# Flutter-v1.net
KiCad netlist of a schematic drawn in EAGLE
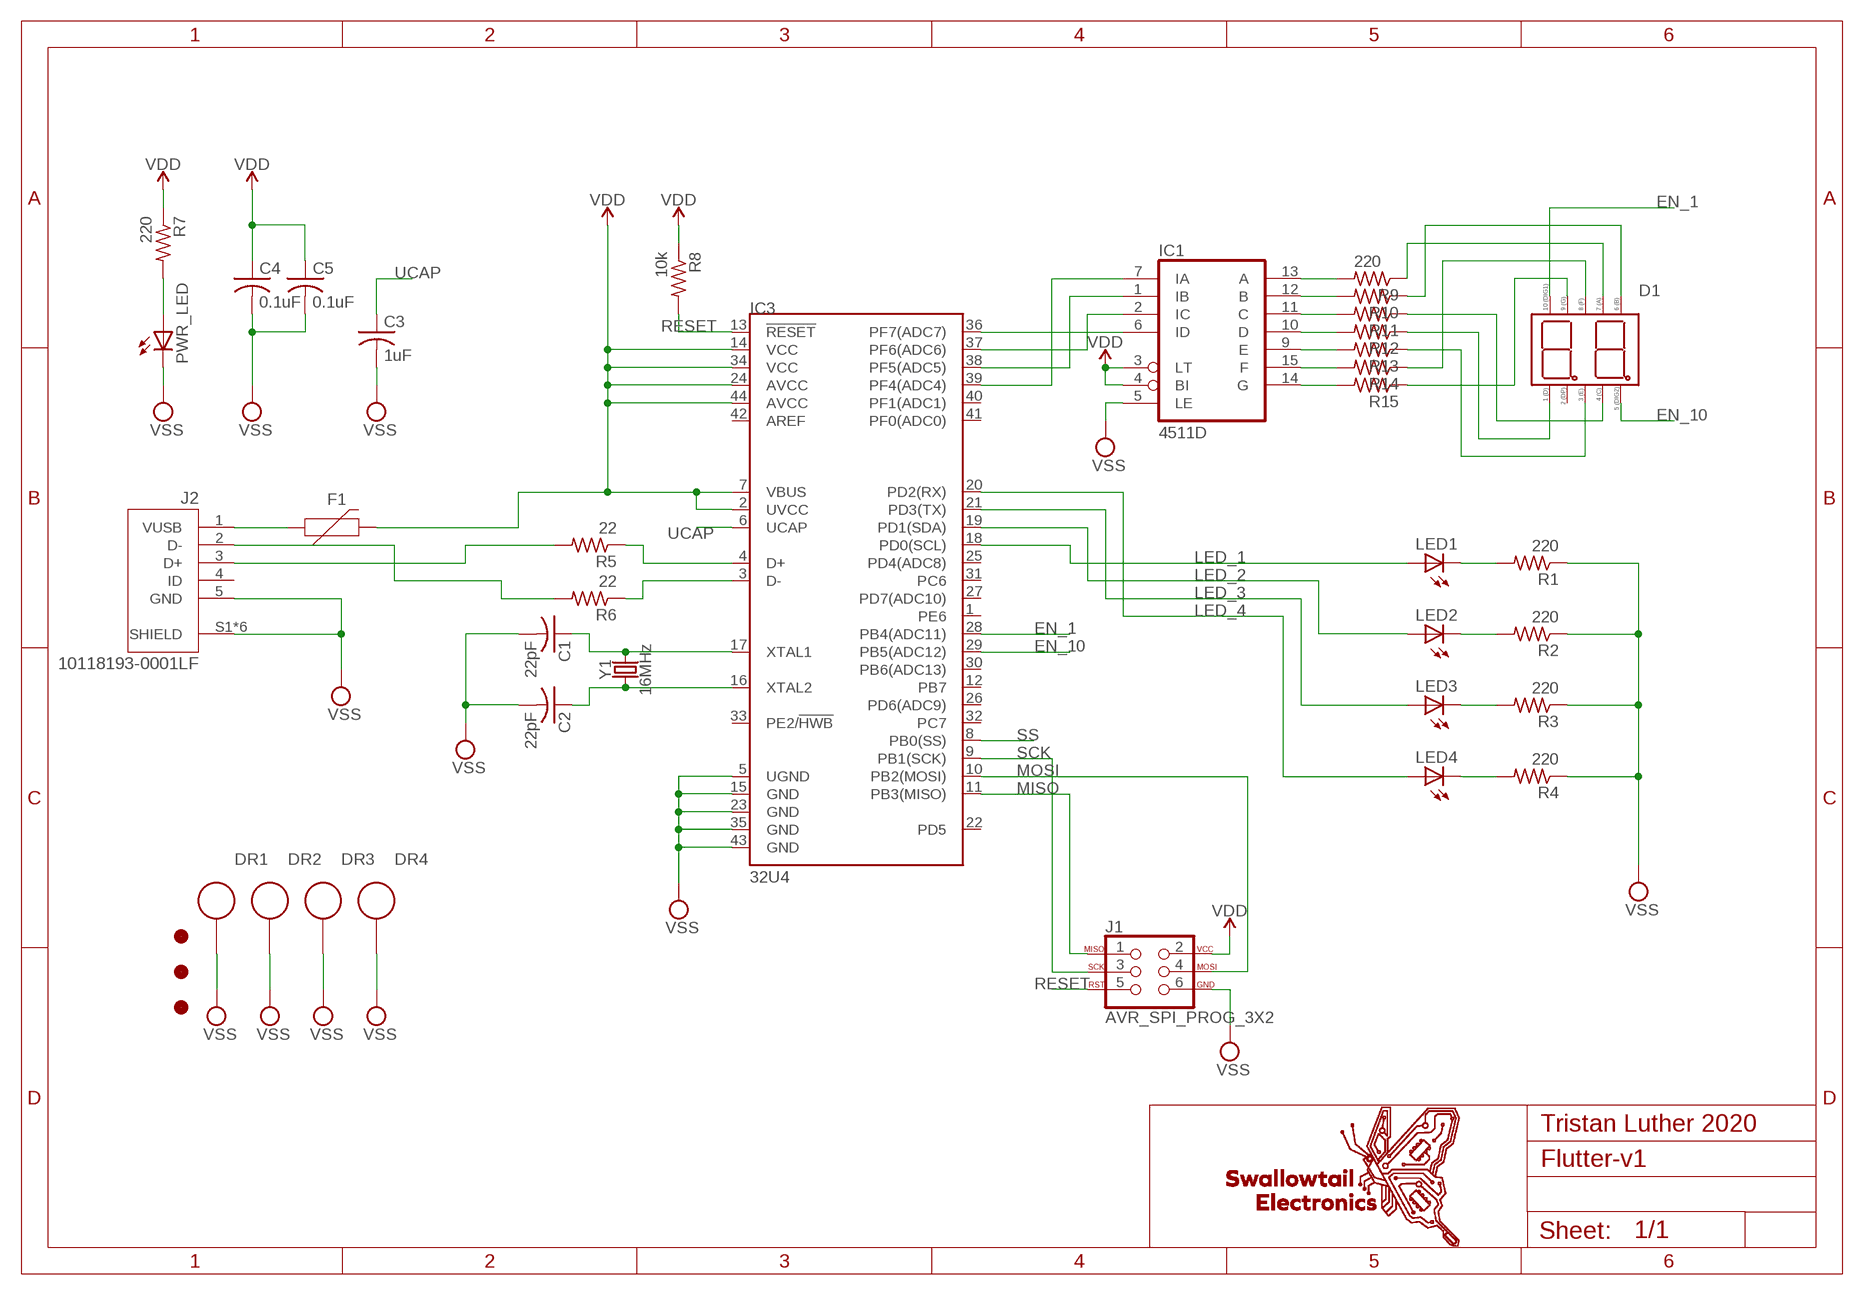
[diagram p0: schematic, sheet 1]

(export (version "E")
  (design (tool "Eeschema 10.0.6"))
  (components
    (comp (ref "C1")
      (value "22pF")
      (footprint "eagle-import:C0805")
      (libsource (lib "eagle-import") (part "C-USC0805"))
    )
    (comp (ref "C2")
      (value "22pF")
      (footprint "eagle-import:C0805")
      (libsource (lib "eagle-import") (part "C-USC0805"))
    )
    (comp (ref "C3")
      (value "1uF")
      (footprint "eagle-import:C0805")
      (libsource (lib "eagle-import") (part "C-USC0805"))
    )
    (comp (ref "C4")
      (value "0.1uF")
      (footprint "eagle-import:C0805")
      (libsource (lib "eagle-import") (part "C-USC0805"))
    )
    (comp (ref "C5")
      (value "0.1uF")
      (footprint "eagle-import:C0805")
      (libsource (lib "eagle-import") (part "C-USC0805"))
    )
    (comp (ref "D1")
      (value "4201AS")
      (footprint "eagle-import:4201AS")
      (libsource (lib "eagle-import") (part "4201AS"))
    )
    (comp (ref "DR1")
      (value "3MM_DRILL_GND")
      (footprint "eagle-import:3MM_DRILL_GND")
      (libsource (lib "eagle-import") (part "3MM_DRILL_GND"))
    )
    (comp (ref "DR2")
      (value "3MM_DRILL_GND")
      (footprint "eagle-import:3MM_DRILL_GND")
      (libsource (lib "eagle-import") (part "3MM_DRILL_GND"))
    )
    (comp (ref "DR3")
      (value "3MM_DRILL_GND")
      (footprint "eagle-import:3MM_DRILL_GND")
      (libsource (lib "eagle-import") (part "3MM_DRILL_GND"))
    )
    (comp (ref "DR4")
      (value "3MM_DRILL_GND")
      (footprint "eagle-import:3MM_DRILL_GND")
      (libsource (lib "eagle-import") (part "3MM_DRILL_GND"))
    )
    (comp (ref "F1")
      (value "6V/0.5A")
      (footprint "eagle-import:1206")
      (libsource (lib "eagle-import") (part "PPTC_HALF-AMP"))
    )
    (comp (ref "IC1")
      (value "4511D")
      (footprint "eagle-import:SO16")
      (libsource (lib "eagle-import") (part "4511D"))
    )
    (comp (ref "IC3")
      (value "32U4")
      (footprint "eagle-import:TQFP44")
      (libsource (lib "eagle-import") (part "ATMEGA32U4TQFP-44"))
    )
    (comp (ref "J1")
      (value "AVR_SPI_PROG_3X2")
      (footprint "eagle-import:2X3-NS")
      (libsource (lib "eagle-import") (part "AVR_SPI_PROG_3X2"))
    )
    (comp (ref "J2")
      (value "10118193-0001LF")
      (footprint "eagle-import:FCI_10118193-0001LF")
      (fields (field (name "MF") "Amphenol ICC"))
      (libsource (lib "eagle-import") (part "10118193-0001LF"))
    )
    (comp (ref "LED1")
      (value "LED5MM")
      (footprint "eagle-import:LED5MM")
      (libsource (lib "eagle-import") (part "LED5MM"))
    )
    (comp (ref "LED2")
      (value "LED5MM")
      (footprint "eagle-import:LED5MM")
      (libsource (lib "eagle-import") (part "LED5MM"))
    )
    (comp (ref "LED3")
      (value "LED5MM")
      (footprint "eagle-import:LED5MM")
      (libsource (lib "eagle-import") (part "LED5MM"))
    )
    (comp (ref "LED4")
      (value "LED5MM")
      (footprint "eagle-import:LED5MM")
      (libsource (lib "eagle-import") (part "LED5MM"))
    )
    (comp (ref "PWR_LED")
      (value "LEDCHIPLED_0603")
      (footprint "eagle-import:CHIPLED_0603")
      (libsource (lib "eagle-import") (part "LEDCHIPLED_0603"))
    )
    (comp (ref "R1")
      (value "220")
      (footprint "eagle-import:M0805")
      (libsource (lib "eagle-import") (part "R-US_M0805"))
    )
    (comp (ref "R2")
      (value "220")
      (footprint "eagle-import:M0805")
      (libsource (lib "eagle-import") (part "R-US_M0805"))
    )
    (comp (ref "R3")
      (value "220")
      (footprint "eagle-import:M0805")
      (libsource (lib "eagle-import") (part "R-US_M0805"))
    )
    (comp (ref "R4")
      (value "220")
      (footprint "eagle-import:M0805")
      (libsource (lib "eagle-import") (part "R-US_M0805"))
    )
    (comp (ref "R5")
      (value "22")
      (footprint "eagle-import:M0805")
      (libsource (lib "eagle-import") (part "R-US_M0805"))
    )
    (comp (ref "R6")
      (value "22")
      (footprint "eagle-import:M0805")
      (libsource (lib "eagle-import") (part "R-US_M0805"))
    )
    (comp (ref "R7")
      (value "220")
      (footprint "eagle-import:M0805")
      (libsource (lib "eagle-import") (part "R-US_M0805"))
    )
    (comp (ref "R8")
      (value "10k")
      (footprint "eagle-import:M0805")
      (libsource (lib "eagle-import") (part "R-US_M0805"))
    )
    (comp (ref "R9")
      (value "220")
      (footprint "eagle-import:M0805")
      (libsource (lib "eagle-import") (part "R-US_M0805"))
    )
    (comp (ref "R10")
      (value "220")
      (footprint "eagle-import:M0805")
      (libsource (lib "eagle-import") (part "R-US_M0805"))
    )
    (comp (ref "R11")
      (value "220")
      (footprint "eagle-import:M0805")
      (libsource (lib "eagle-import") (part "R-US_M0805"))
    )
    (comp (ref "R12")
      (value "220")
      (footprint "eagle-import:M0805")
      (libsource (lib "eagle-import") (part "R-US_M0805"))
    )
    (comp (ref "R13")
      (value "220")
      (footprint "eagle-import:M0805")
      (libsource (lib "eagle-import") (part "R-US_M0805"))
    )
    (comp (ref "R14")
      (value "220")
      (footprint "eagle-import:M0805")
      (libsource (lib "eagle-import") (part "R-US_M0805"))
    )
    (comp (ref "R15")
      (value "220")
      (footprint "eagle-import:M0805")
      (libsource (lib "eagle-import") (part "R-US_M0805"))
    )
    (comp (ref "U$4")
      (value "FIDUCIAL_MARKER")
      (footprint "eagle-import:FIDUCIAL_MARKER")
      (libsource (lib "eagle-import") (part "FIDUCIAL_MARKER"))
    )
    (comp (ref "U$5")
      (value "FIDUCIAL_MARKER")
      (footprint "eagle-import:FIDUCIAL_MARKER")
      (libsource (lib "eagle-import") (part "FIDUCIAL_MARKER"))
    )
    (comp (ref "U$6")
      (value "FIDUCIAL_MARKER")
      (footprint "eagle-import:FIDUCIAL_MARKER")
      (libsource (lib "eagle-import") (part "FIDUCIAL_MARKER"))
    )
    (comp (ref "Y1")
      (value "16MHz")
      (footprint "eagle-import:CRYSTAL-SMD-5X3.2-4PAD")
      (libsource (lib "eagle-import") (part "CRYSTAL-16MHZSMD-5X3.2"))
    )
  )
  (nets
    (net (code "1") (name "/EN_1") (class "Default")
      (node (ref "D1") (pin "10") (pinfunction "10_10") (pintype "bidirectional"))
      (node (ref "IC3") (pin "28") (pinfunction "PB4(ADC11)_28") (pintype "bidirectional"))
    )
    (net (code "2") (name "/EN_10") (class "Default")
      (node (ref "D1") (pin "5") (pinfunction "5(DIG_2)_5") (pintype "bidirectional"))
      (node (ref "IC3") (pin "29") (pinfunction "PB5(ADC12)_29") (pintype "bidirectional"))
    )
    (net (code "3") (name "/LED_1") (class "Default")
      (node (ref "IC3") (pin "18") (pinfunction "PD0(SCL)_18") (pintype "bidirectional"))
      (node (ref "LED1") (pin "A") (pinfunction "A_A") (pintype "passive"))
    )
    (net (code "4") (name "/LED_2") (class "Default")
      (node (ref "IC3") (pin "19") (pinfunction "PD1(SDA)_19") (pintype "bidirectional"))
      (node (ref "LED2") (pin "A") (pinfunction "A_A") (pintype "passive"))
    )
    (net (code "5") (name "/LED_3") (class "Default")
      (node (ref "IC3") (pin "21") (pinfunction "PD3(TX)_21") (pintype "bidirectional"))
      (node (ref "LED3") (pin "A") (pinfunction "A_A") (pintype "passive"))
    )
    (net (code "6") (name "/LED_4") (class "Default")
      (node (ref "IC3") (pin "20") (pinfunction "PD2(RX)_20") (pintype "bidirectional"))
      (node (ref "LED4") (pin "A") (pinfunction "A_A") (pintype "passive"))
    )
    (net (code "7") (name "/MISO") (class "Default")
      (node (ref "IC3") (pin "11") (pinfunction "PB3(MISO)_11") (pintype "bidirectional"))
      (node (ref "J1") (pin "1") (pinfunction "1_1") (pintype "passive"))
    )
    (net (code "8") (name "/MOSI") (class "Default")
      (node (ref "IC3") (pin "10") (pinfunction "PB2(MOSI)_10") (pintype "bidirectional"))
      (node (ref "J1") (pin "4") (pinfunction "4_4") (pintype "passive"))
    )
    (net (code "9") (name "/RESET") (class "Default")
      (node (ref "IC3") (pin "13") (pinfunction "~{RESET}_13") (pintype "bidirectional"))
      (node (ref "J1") (pin "5") (pinfunction "5_5") (pintype "passive"))
      (node (ref "R8") (pin "2") (pinfunction "2_2") (pintype "passive"))
    )
    (net (code "10") (name "/SCK") (class "Default")
      (node (ref "IC3") (pin "9") (pinfunction "PB1(SCK)_9") (pintype "bidirectional"))
      (node (ref "J1") (pin "3") (pinfunction "3_3") (pintype "passive"))
    )
    (net (code "11") (name "/SS") (class "Default")
      (node (ref "IC3") (pin "8") (pinfunction "PB0(SS)_8") (pintype "bidirectional"))
    )
    (net (code "12") (name "/UCAP") (class "Default")
      (node (ref "C3") (pin "1") (pinfunction "1_1") (pintype "passive"))
      (node (ref "IC3") (pin "6") (pinfunction "UCAP_6") (pintype "bidirectional"))
    )
    (net (code "13") (name "Net-(D1-1(D))") (class "Default")
      (node (ref "D1") (pin "1") (pinfunction "1(D)_1") (pintype "bidirectional"))
      (node (ref "R12") (pin "1") (pinfunction "1_1") (pintype "passive"))
    )
    (net (code "14") (name "Net-(D1-3(E))") (class "Default")
      (node (ref "D1") (pin "3") (pinfunction "3(E)_3") (pintype "bidirectional"))
      (node (ref "R13") (pin "1") (pinfunction "1_1") (pintype "passive"))
    )
    (net (code "15") (name "Net-(D1-4(C))") (class "Default")
      (node (ref "D1") (pin "4") (pinfunction "4(C)_4") (pintype "bidirectional"))
      (node (ref "R11") (pin "1") (pinfunction "1_1") (pintype "passive"))
    )
    (net (code "16") (name "Net-(D1-6(B))") (class "Default")
      (node (ref "D1") (pin "6") (pinfunction "6(B)_6") (pintype "bidirectional"))
      (node (ref "R10") (pin "1") (pinfunction "1_1") (pintype "passive"))
    )
    (net (code "17") (name "Net-(D1-7(A))") (class "Default")
      (node (ref "D1") (pin "7") (pinfunction "7(A)_7") (pintype "bidirectional"))
      (node (ref "R9") (pin "1") (pinfunction "1_1") (pintype "passive"))
    )
    (net (code "18") (name "Net-(D1-8(F))") (class "Default")
      (node (ref "D1") (pin "8") (pinfunction "8(F)_8") (pintype "bidirectional"))
      (node (ref "R14") (pin "1") (pinfunction "1_1") (pintype "passive"))
    )
    (net (code "19") (name "Net-(D1-9(G))") (class "Default")
      (node (ref "D1") (pin "9") (pinfunction "9(G)_9") (pintype "bidirectional"))
      (node (ref "R15") (pin "1") (pinfunction "1_1") (pintype "passive"))
    )
    (net (code "20") (name "Net-(IC1A-A)") (class "Default")
      (node (ref "IC1") (pin "13") (pinfunction "A_13") (pintype "output"))
      (node (ref "R9") (pin "2") (pinfunction "2_2") (pintype "passive"))
    )
    (net (code "21") (name "Net-(IC1A-B)") (class "Default")
      (node (ref "IC1") (pin "12") (pinfunction "B_12") (pintype "output"))
      (node (ref "R10") (pin "2") (pinfunction "2_2") (pintype "passive"))
    )
    (net (code "22") (name "Net-(IC1A-C)") (class "Default")
      (node (ref "IC1") (pin "11") (pinfunction "C_11") (pintype "output"))
      (node (ref "R11") (pin "2") (pinfunction "2_2") (pintype "passive"))
    )
    (net (code "23") (name "Net-(IC1A-D)") (class "Default")
      (node (ref "IC1") (pin "10") (pinfunction "D_10") (pintype "output"))
      (node (ref "R12") (pin "2") (pinfunction "2_2") (pintype "passive"))
    )
    (net (code "24") (name "Net-(IC1A-E)") (class "Default")
      (node (ref "IC1") (pin "9") (pinfunction "E_9") (pintype "output"))
      (node (ref "R13") (pin "2") (pinfunction "2_2") (pintype "passive"))
    )
    (net (code "25") (name "Net-(IC1A-F)") (class "Default")
      (node (ref "IC1") (pin "15") (pinfunction "F_15") (pintype "output"))
      (node (ref "R14") (pin "2") (pinfunction "2_2") (pintype "passive"))
    )
    (net (code "26") (name "Net-(IC1A-G)") (class "Default")
      (node (ref "IC1") (pin "14") (pinfunction "G_14") (pintype "output"))
      (node (ref "R15") (pin "2") (pinfunction "2_2") (pintype "passive"))
    )
    (net (code "27") (name "Net-(IC1A-IA)") (class "Default")
      (node (ref "IC1") (pin "7") (pinfunction "IA_7") (pintype "input"))
      (node (ref "IC3") (pin "39") (pinfunction "PF4(ADC4)_39") (pintype "bidirectional"))
    )
    (net (code "28") (name "Net-(IC1A-IB)") (class "Default")
      (node (ref "IC1") (pin "1") (pinfunction "IB_1") (pintype "input"))
      (node (ref "IC3") (pin "38") (pinfunction "PF5(ADC5)_38") (pintype "bidirectional"))
    )
    (net (code "29") (name "Net-(IC1A-IC)") (class "Default")
      (node (ref "IC1") (pin "2") (pinfunction "IC_2") (pintype "input"))
      (node (ref "IC3") (pin "37") (pinfunction "PF6(ADC6)_37") (pintype "bidirectional"))
    )
    (net (code "30") (name "Net-(IC1A-ID)") (class "Default")
      (node (ref "IC1") (pin "6") (pinfunction "ID_6") (pintype "input"))
      (node (ref "IC3") (pin "36") (pinfunction "PF7(ADC7)_36") (pintype "bidirectional"))
    )
    (net (code "31") (name "Net-(IC3-D+)") (class "Default")
      (node (ref "IC3") (pin "4") (pinfunction "D+_4") (pintype "bidirectional"))
      (node (ref "R5") (pin "1") (pinfunction "1_1") (pintype "passive"))
    )
    (net (code "32") (name "Net-(IC3-D-)") (class "Default")
      (node (ref "IC3") (pin "3") (pinfunction "D-_3") (pintype "bidirectional"))
      (node (ref "R6") (pin "1") (pinfunction "1_1") (pintype "passive"))
    )
    (net (code "33") (name "Net-(IC3-XTAL1)") (class "Default")
      (node (ref "C1") (pin "1") (pinfunction "1_1") (pintype "passive"))
      (node (ref "IC3") (pin "17") (pinfunction "XTAL1_17") (pintype "bidirectional"))
      (node (ref "Y1") (pin "3") (pinfunction "2_3") (pintype "passive"))
    )
    (net (code "34") (name "Net-(IC3-XTAL2)") (class "Default")
      (node (ref "C2") (pin "1") (pinfunction "1_1") (pintype "passive"))
      (node (ref "IC3") (pin "16") (pinfunction "XTAL2_16") (pintype "bidirectional"))
      (node (ref "Y1") (pin "1") (pinfunction "1_1") (pintype "passive"))
    )
    (net (code "35") (name "Net-(J2-D+)") (class "Default")
      (node (ref "J2") (pin "3") (pinfunction "D+_3") (pintype "passive"))
      (node (ref "R5") (pin "2") (pinfunction "2_2") (pintype "passive"))
    )
    (net (code "36") (name "Net-(J2-D-)") (class "Default")
      (node (ref "J2") (pin "2") (pinfunction "D-_2") (pintype "passive"))
      (node (ref "R6") (pin "2") (pinfunction "2_2") (pintype "passive"))
    )
    (net (code "37") (name "Net-(J2-VUSB)") (class "Default")
      (node (ref "F1") (pin "1") (pinfunction "1_1") (pintype "bidirectional"))
      (node (ref "J2") (pin "1") (pinfunction "VUSB_1") (pintype "passive"))
    )
    (net (code "38") (name "Net-(LED1-C)") (class "Default")
      (node (ref "LED1") (pin "K") (pinfunction "C_K") (pintype "passive"))
      (node (ref "R1") (pin "2") (pinfunction "2_2") (pintype "passive"))
    )
    (net (code "39") (name "Net-(LED2-C)") (class "Default")
      (node (ref "LED2") (pin "K") (pinfunction "C_K") (pintype "passive"))
      (node (ref "R2") (pin "2") (pinfunction "2_2") (pintype "passive"))
    )
    (net (code "40") (name "Net-(LED3-C)") (class "Default")
      (node (ref "LED3") (pin "K") (pinfunction "C_K") (pintype "passive"))
      (node (ref "R3") (pin "2") (pinfunction "2_2") (pintype "passive"))
    )
    (net (code "41") (name "Net-(LED4-C)") (class "Default")
      (node (ref "LED4") (pin "K") (pinfunction "C_K") (pintype "passive"))
      (node (ref "R4") (pin "2") (pinfunction "2_2") (pintype "passive"))
    )
    (net (code "42") (name "Net-(PWR_LED-PadA)") (class "Default")
      (node (ref "PWR_LED") (pin "A") (pinfunction "A_A") (pintype "passive"))
      (node (ref "R7") (pin "2") (pinfunction "2_2") (pintype "passive"))
    )
    (net (code "43") (name "VDD") (class "Default")
      (node (ref "C4") (pin "1") (pinfunction "1_1") (pintype "passive"))
      (node (ref "C5") (pin "1") (pinfunction "1_1") (pintype "passive"))
      (node (ref "F1") (pin "2") (pinfunction "2_2") (pintype "bidirectional"))
      (node (ref "IC1") (pin "3") (pinfunction "LT_3") (pintype "input"))
      (node (ref "IC1") (pin "4") (pinfunction "BI_4") (pintype "input"))
      (node (ref "IC3") (pin "14") (pinfunction "VCC_14") (pintype "bidirectional"))
      (node (ref "IC3") (pin "2") (pinfunction "UVCC_2") (pintype "bidirectional"))
      (node (ref "IC3") (pin "24") (pinfunction "AVCC_24") (pintype "bidirectional"))
      (node (ref "IC3") (pin "34") (pinfunction "VCC_34") (pintype "bidirectional"))
      (node (ref "IC3") (pin "44") (pinfunction "AVCC_44") (pintype "bidirectional"))
      (node (ref "IC3") (pin "7") (pinfunction "VBUS_7") (pintype "bidirectional"))
      (node (ref "J1") (pin "2") (pinfunction "2_2") (pintype "passive"))
      (node (ref "R7") (pin "1") (pinfunction "1_1") (pintype "passive"))
      (node (ref "R8") (pin "1") (pinfunction "1_1") (pintype "passive"))
    )
    (net (code "44") (name "VSS") (class "Default")
      (node (ref "C1") (pin "2") (pinfunction "2_2") (pintype "passive"))
      (node (ref "C2") (pin "2") (pinfunction "2_2") (pintype "passive"))
      (node (ref "C3") (pin "2") (pinfunction "2_2") (pintype "passive"))
      (node (ref "C4") (pin "2") (pinfunction "2_2") (pintype "passive"))
      (node (ref "C5") (pin "2") (pinfunction "2_2") (pintype "passive"))
      (node (ref "DR1") (pin "DR") (pinfunction "D$1_DR") (pintype "bidirectional"))
      (node (ref "DR2") (pin "DR") (pinfunction "D$1_DR") (pintype "bidirectional"))
      (node (ref "DR3") (pin "DR") (pinfunction "D$1_DR") (pintype "bidirectional"))
      (node (ref "DR4") (pin "DR") (pinfunction "D$1_DR") (pintype "bidirectional"))
      (node (ref "IC1") (pin "5") (pinfunction "LE_5") (pintype "input"))
      (node (ref "IC3") (pin "15") (pinfunction "GND_15") (pintype "bidirectional"))
      (node (ref "IC3") (pin "23") (pinfunction "GND_23") (pintype "bidirectional"))
      (node (ref "IC3") (pin "35") (pinfunction "GND_35") (pintype "bidirectional"))
      (node (ref "IC3") (pin "43") (pinfunction "GND_43") (pintype "bidirectional"))
      (node (ref "IC3") (pin "5") (pinfunction "UGND_5") (pintype "bidirectional"))
      (node (ref "J1") (pin "6") (pinfunction "6_6") (pintype "passive"))
      (node (ref "J2") (pin "5") (pinfunction "GND_5") (pintype "passive"))
      (node (ref "J2") (pin "S1") (pinfunction "SHIELD_S1") (pintype "passive"))
      (node (ref "J2") (pin "S2") (pinfunction "SHIELD_S2") (pintype "passive"))
      (node (ref "J2") (pin "S3") (pinfunction "SHIELD_S3") (pintype "passive"))
      (node (ref "J2") (pin "S4") (pinfunction "SHIELD_S4") (pintype "passive"))
      (node (ref "J2") (pin "S5") (pinfunction "SHIELD_S5") (pintype "passive"))
      (node (ref "J2") (pin "S6") (pinfunction "SHIELD_S6") (pintype "passive"))
      (node (ref "PWR_LED") (pin "C") (pinfunction "C_C") (pintype "passive"))
      (node (ref "R1") (pin "1") (pinfunction "1_1") (pintype "passive"))
      (node (ref "R2") (pin "1") (pinfunction "1_1") (pintype "passive"))
      (node (ref "R3") (pin "1") (pinfunction "1_1") (pintype "passive"))
      (node (ref "R4") (pin "1") (pinfunction "1_1") (pintype "passive"))
    )
    (net (code "45") (name "unconnected-(D1-2(DP)-Pad2)") (class "Default")
      (node (ref "D1") (pin "2") (pinfunction "2(DP)_2") (pintype "bidirectional"))
    )
    (net (code "46") (name "unconnected-(IC3-AREF-Pad42)") (class "Default")
      (node (ref "IC3") (pin "42") (pinfunction "AREF_42") (pintype "bidirectional"))
    )
    (net (code "47") (name "unconnected-(IC3-PB6(ADC13)-Pad30)") (class "Default")
      (node (ref "IC3") (pin "30") (pinfunction "PB6(ADC13)_30") (pintype "bidirectional"))
    )
    (net (code "48") (name "unconnected-(IC3-PB7-Pad12)") (class "Default")
      (node (ref "IC3") (pin "12") (pinfunction "PB7_12") (pintype "bidirectional"))
    )
    (net (code "49") (name "unconnected-(IC3-PC6-Pad31)") (class "Default")
      (node (ref "IC3") (pin "31") (pinfunction "PC6_31") (pintype "bidirectional"))
    )
    (net (code "50") (name "unconnected-(IC3-PC7-Pad32)") (class "Default")
      (node (ref "IC3") (pin "32") (pinfunction "PC7_32") (pintype "bidirectional"))
    )
    (net (code "51") (name "unconnected-(IC3-PD4(ADC8)-Pad25)") (class "Default")
      (node (ref "IC3") (pin "25") (pinfunction "PD4(ADC8)_25") (pintype "bidirectional"))
    )
    (net (code "52") (name "unconnected-(IC3-PD5-Pad22)") (class "Default")
      (node (ref "IC3") (pin "22") (pinfunction "PD5_22") (pintype "bidirectional"))
    )
    (net (code "53") (name "unconnected-(IC3-PD6(ADC9)-Pad26)") (class "Default")
      (node (ref "IC3") (pin "26") (pinfunction "PD6(ADC9)_26") (pintype "bidirectional"))
    )
    (net (code "54") (name "unconnected-(IC3-PD7(ADC10)-Pad27)") (class "Default")
      (node (ref "IC3") (pin "27") (pinfunction "PD7(ADC10)_27") (pintype "bidirectional"))
    )
    (net (code "55") (name "unconnected-(IC3-PE2{slash}~{HWB}-Pad33)") (class "Default")
      (node (ref "IC3") (pin "33") (pinfunction "PE2/~{HWB}_33") (pintype "bidirectional"))
    )
    (net (code "56") (name "unconnected-(IC3-PE6-Pad1)") (class "Default")
      (node (ref "IC3") (pin "1") (pinfunction "PE6_1") (pintype "bidirectional"))
    )
    (net (code "57") (name "unconnected-(IC3-PF0(ADC0)-Pad41)") (class "Default")
      (node (ref "IC3") (pin "41") (pinfunction "PF0(ADC0)_41") (pintype "bidirectional"))
    )
    (net (code "58") (name "unconnected-(IC3-PF1(ADC1)-Pad40)") (class "Default")
      (node (ref "IC3") (pin "40") (pinfunction "PF1(ADC1)_40") (pintype "bidirectional"))
    )
    (net (code "59") (name "unconnected-(J2-ID-Pad4)") (class "Default")
      (node (ref "J2") (pin "4") (pinfunction "ID_4") (pintype "passive"))
    )
  )
)
